# X16-ESC-Controller.net
KiCad netlist of a schematic drawn in EAGLE
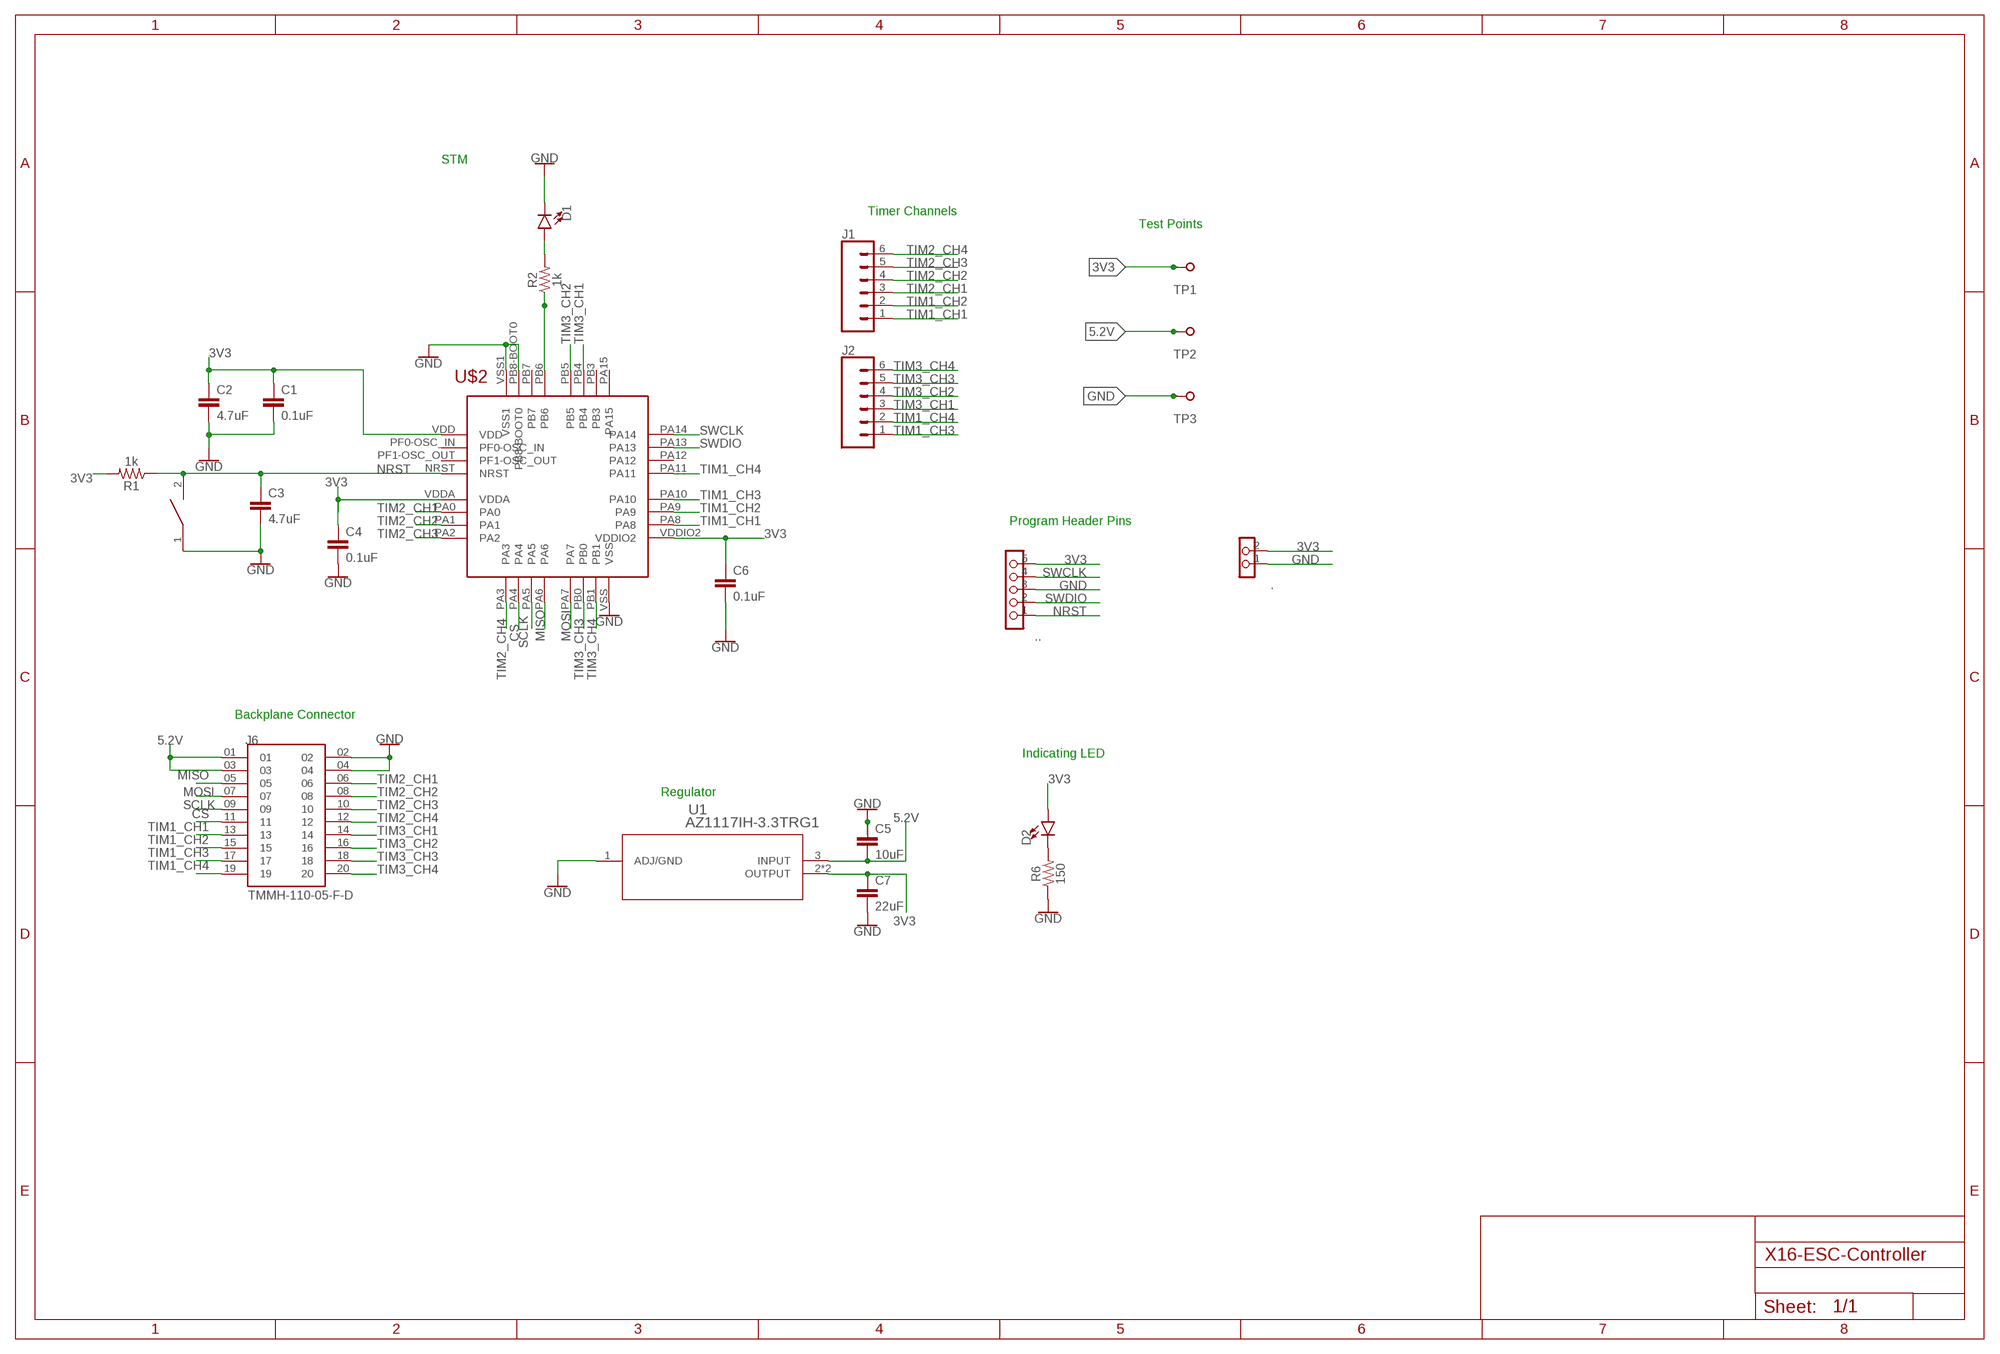
[diagram p0: schematic, sheet 1]

(export (version "E")
  (design (tool "Eeschema 10.0.6"))
  (components
    (comp (ref ".")
      (value "TEST_PIN-1X2")
      (footprint "eagle-import:1X02")
      (libsource (lib "eagle-import") (part "TEST_PIN-1X2"))
    )
    (comp (ref "..")
      (value "TEST_PIN-1X5")
      (footprint "eagle-import:1X05")
      (libsource (lib "eagle-import") (part "TEST_PIN-1X5"))
    )
    (comp (ref "C1")
      (value "0.1uF")
      (footprint "eagle-import:0603")
      (libsource (lib "eagle-import") (part "4.7PF-0603-50V-5%"))
    )
    (comp (ref "C2")
      (value "4.7uF")
      (footprint "eagle-import:0603")
      (libsource (lib "eagle-import") (part "4.7PF-0603-50V-5%"))
    )
    (comp (ref "C3")
      (value "4.7uF")
      (footprint "eagle-import:0603")
      (libsource (lib "eagle-import") (part "4.7PF-0603-50V-5%"))
    )
    (comp (ref "C4")
      (value "0.1uF")
      (footprint "eagle-import:0603")
      (libsource (lib "eagle-import") (part "4.7PF-0603-50V-5%"))
    )
    (comp (ref "C5")
      (value "10uF")
      (footprint "eagle-import:0603")
      (libsource (lib "eagle-import") (part "4.7PF-0603-50V-5%"))
    )
    (comp (ref "C6")
      (value "0.1uF")
      (footprint "eagle-import:0603")
      (libsource (lib "eagle-import") (part "4.7PF-0603-50V-5%"))
    )
    (comp (ref "C7")
      (value "22uF")
      (footprint "eagle-import:0603")
      (libsource (lib "eagle-import") (part "4.7PF-0603-50V-5%"))
    )
    (comp (ref "D1")
      (value "Green")
      (footprint "eagle-import:LED-0805")
      (libsource (lib "eagle-import") (part "LED-GREEN0805-PG"))
    )
    (comp (ref "D2")
      (value "Green")
      (footprint "eagle-import:LED-0805")
      (libsource (lib "eagle-import") (part "LED-GREEN0805-PG"))
    )
    (comp (ref "J1")
      (value "CONN_06NO_SILK_NO_POP")
      (footprint "eagle-import:1X06_NO_SILK")
      (libsource (lib "eagle-import") (part "CONN_06NO_SILK_NO_POP"))
    )
    (comp (ref "J2")
      (value "CONN_06NO_SILK_NO_POP")
      (footprint "eagle-import:1X06_NO_SILK")
      (libsource (lib "eagle-import") (part "CONN_06NO_SILK_NO_POP"))
    )
    (comp (ref "J6")
      (value "TMMH-110-05-F-D")
      (footprint "eagle-import:SAMTEC_TMMH-110-05-F-D")
      (fields (field (name "MANUFACTURER") "Samtec"))
      (libsource (lib "eagle-import") (part "TMMH-110-05-F-D"))
    )
    (comp (ref "R1")
      (value "1k")
      (footprint "eagle-import:0603")
      (libsource (lib "eagle-import") (part "2.55KOHM-0603-1/10W-1%"))
    )
    (comp (ref "R2")
      (value "1k")
      (footprint "eagle-import:0603")
      (libsource (lib "eagle-import") (part "2.55KOHM-0603-1/10W-1%"))
    )
    (comp (ref "R6")
      (value "150")
      (footprint "eagle-import:0603")
      (libsource (lib "eagle-import") (part "2.55KOHM-0603-1/10W-1%"))
    )
    (comp (ref "TP1")
      (value "TESTPOINT_5.04MM")
      (footprint "eagle-import:TESTPOINT_5.04MM")
      (libsource (lib "eagle-import") (part "TESTPOINT_5.04MM"))
    )
    (comp (ref "TP2")
      (value "TESTPOINT_5.04MM")
      (footprint "eagle-import:TESTPOINT_5.04MM")
      (libsource (lib "eagle-import") (part "TESTPOINT_5.04MM"))
    )
    (comp (ref "TP3")
      (value "TESTPOINT_5.04MM")
      (footprint "eagle-import:TESTPOINT_5.04MM")
      (libsource (lib "eagle-import") (part "TESTPOINT_5.04MM"))
    )
    (comp (ref "U$2")
      (value "IC_STM32F042K6T6")
      (footprint "eagle-import:STM32F042K6T6")
      (libsource (lib "eagle-import") (part "IC_STM32F042K6T6"))
    )
    (comp (ref "U$3")
      (value "SWITCH_DISCRETECOMPONENTS")
      (footprint "eagle-import:DISCRETECOMPONENTS_SW_2512")
      (libsource (lib "eagle-import") (part "SWITCH_DISCRETECOMPONENTS"))
    )
    (comp (ref "U1")
      (value "AZ1117IH-3.3TRG1")
      (footprint "eagle-import:SOT223_AZ1117I_6P5X3P5_DIO")
      (fields (field (name "COPYRIGHT") "Copyright (C) 2023 Ultra Librarian. All rights reserved."))
      (libsource (lib "eagle-import") (part "AZ1117IH-3.3TRG1"))
    )
  )
  (nets
    (net (code "1") (name "/CS") (class "Default")
      (node (ref "J6") (pin "11") (pinfunction "11_11") (pintype "passive"))
      (node (ref "U$2") (pin "PA4") (pinfunction "PA4_PA4") (pintype "bidirectional"))
    )
    (net (code "2") (name "/MISO") (class "Default")
      (node (ref "J6") (pin "05") (pinfunction "05_05") (pintype "passive"))
      (node (ref "U$2") (pin "PA6") (pinfunction "PA6_PA6") (pintype "bidirectional"))
    )
    (net (code "3") (name "/MOSI") (class "Default")
      (node (ref "J6") (pin "07") (pinfunction "07_07") (pintype "passive"))
      (node (ref "U$2") (pin "PA7") (pinfunction "PA7_PA7") (pintype "bidirectional"))
    )
    (net (code "4") (name "/NRST") (class "Default")
      (node (ref "..") (pin "1") (pinfunction "1_1") (pintype "passive"))
      (node (ref "C3") (pin "1") (pinfunction "1_1") (pintype "passive"))
      (node (ref "R1") (pin "1") (pinfunction "1_1") (pintype "passive"))
      (node (ref "U$2") (pin "NRST") (pinfunction "NRST_NRST") (pintype "bidirectional"))
      (node (ref "U$3") (pin "2") (pinfunction "P$2_2") (pintype "bidirectional"))
    )
    (net (code "5") (name "/SCLK") (class "Default")
      (node (ref "J6") (pin "09") (pinfunction "09_09") (pintype "passive"))
      (node (ref "U$2") (pin "PA5") (pinfunction "PA5_PA5") (pintype "bidirectional"))
    )
    (net (code "6") (name "/SWCLK") (class "Default")
      (node (ref "..") (pin "4") (pinfunction "4_4") (pintype "passive"))
      (node (ref "U$2") (pin "PA14") (pinfunction "PA14_PA14") (pintype "bidirectional"))
    )
    (net (code "7") (name "/SWDIO") (class "Default")
      (node (ref "..") (pin "2") (pinfunction "2_2") (pintype "passive"))
      (node (ref "U$2") (pin "PA13") (pinfunction "PA13_PA13") (pintype "bidirectional"))
    )
    (net (code "8") (name "/TIM1_CH1") (class "Default")
      (node (ref "J1") (pin "1") (pinfunction "1_1") (pintype "passive"))
      (node (ref "J6") (pin "13") (pinfunction "13_13") (pintype "passive"))
      (node (ref "U$2") (pin "PA8") (pinfunction "PA8_PA8") (pintype "bidirectional"))
    )
    (net (code "9") (name "/TIM1_CH2") (class "Default")
      (node (ref "J1") (pin "2") (pinfunction "2_2") (pintype "passive"))
      (node (ref "J6") (pin "15") (pinfunction "15_15") (pintype "passive"))
      (node (ref "U$2") (pin "PA9") (pinfunction "PA9_PA9") (pintype "bidirectional"))
    )
    (net (code "10") (name "/TIM1_CH3") (class "Default")
      (node (ref "J2") (pin "1") (pinfunction "1_1") (pintype "passive"))
      (node (ref "J6") (pin "17") (pinfunction "17_17") (pintype "passive"))
      (node (ref "U$2") (pin "PA10") (pinfunction "PA10_PA10") (pintype "bidirectional"))
    )
    (net (code "11") (name "/TIM1_CH4") (class "Default")
      (node (ref "J2") (pin "2") (pinfunction "2_2") (pintype "passive"))
      (node (ref "J6") (pin "19") (pinfunction "19_19") (pintype "passive"))
      (node (ref "U$2") (pin "PA11") (pinfunction "PA11_PA11") (pintype "bidirectional"))
    )
    (net (code "12") (name "/TIM2_CH1") (class "Default")
      (node (ref "J1") (pin "3") (pinfunction "3_3") (pintype "passive"))
      (node (ref "J6") (pin "06") (pinfunction "06_06") (pintype "passive"))
      (node (ref "U$2") (pin "PA0") (pinfunction "PA0_PA0") (pintype "bidirectional"))
    )
    (net (code "13") (name "/TIM2_CH2") (class "Default")
      (node (ref "J1") (pin "4") (pinfunction "4_4") (pintype "passive"))
      (node (ref "J6") (pin "08") (pinfunction "08_08") (pintype "passive"))
      (node (ref "U$2") (pin "PA1") (pinfunction "PA1_PA1") (pintype "bidirectional"))
    )
    (net (code "14") (name "/TIM2_CH3") (class "Default")
      (node (ref "J1") (pin "5") (pinfunction "5_5") (pintype "passive"))
      (node (ref "J6") (pin "10") (pinfunction "10_10") (pintype "passive"))
      (node (ref "U$2") (pin "PA2") (pinfunction "PA2_PA2") (pintype "bidirectional"))
    )
    (net (code "15") (name "/TIM2_CH4") (class "Default")
      (node (ref "J1") (pin "6") (pinfunction "6_6") (pintype "passive"))
      (node (ref "J6") (pin "12") (pinfunction "12_12") (pintype "passive"))
      (node (ref "U$2") (pin "PA3") (pinfunction "PA3_PA3") (pintype "bidirectional"))
    )
    (net (code "16") (name "/TIM3_CH1") (class "Default")
      (node (ref "J2") (pin "3") (pinfunction "3_3") (pintype "passive"))
      (node (ref "J6") (pin "14") (pinfunction "14_14") (pintype "passive"))
      (node (ref "U$2") (pin "PB4") (pinfunction "PB4_PB4") (pintype "bidirectional"))
    )
    (net (code "17") (name "/TIM3_CH2") (class "Default")
      (node (ref "J2") (pin "4") (pinfunction "4_4") (pintype "passive"))
      (node (ref "J6") (pin "16") (pinfunction "16_16") (pintype "passive"))
      (node (ref "U$2") (pin "PB5") (pinfunction "PB5_PB5") (pintype "bidirectional"))
    )
    (net (code "18") (name "/TIM3_CH3") (class "Default")
      (node (ref "J2") (pin "5") (pinfunction "5_5") (pintype "passive"))
      (node (ref "J6") (pin "18") (pinfunction "18_18") (pintype "passive"))
      (node (ref "U$2") (pin "PB0") (pinfunction "PB0_PB0") (pintype "bidirectional"))
    )
    (net (code "19") (name "/TIM3_CH4") (class "Default")
      (node (ref "J2") (pin "6") (pinfunction "6_6") (pintype "passive"))
      (node (ref "J6") (pin "20") (pinfunction "20_20") (pintype "passive"))
      (node (ref "U$2") (pin "PB1") (pinfunction "PB1_PB1") (pintype "bidirectional"))
    )
    (net (code "20") (name "3V3") (class "Default")
      (node (ref ".") (pin "2") (pinfunction "2_2") (pintype "passive"))
      (node (ref "..") (pin "5") (pinfunction "5_5") (pintype "passive"))
      (node (ref "C1") (pin "1") (pinfunction "1_1") (pintype "passive"))
      (node (ref "C2") (pin "1") (pinfunction "1_1") (pintype "passive"))
      (node (ref "C4") (pin "1") (pinfunction "1_1") (pintype "passive"))
      (node (ref "C6") (pin "1") (pinfunction "1_1") (pintype "passive"))
      (node (ref "C7") (pin "1") (pinfunction "1_1") (pintype "passive"))
      (node (ref "D2") (pin "A") (pinfunction "A_A") (pintype "passive"))
      (node (ref "R1") (pin "2") (pinfunction "2_2") (pintype "passive"))
      (node (ref "TP1") (pin "TP") (pinfunction "TP_TP") (pintype "input"))
      (node (ref "U$2") (pin "VDD") (pinfunction "VDD_VDD") (pintype "bidirectional"))
      (node (ref "U$2") (pin "VDDA") (pinfunction "VDDA_VDDA") (pintype "bidirectional"))
      (node (ref "U$2") (pin "VDDIO2") (pinfunction "VDDIO2_VDDIO2") (pintype "bidirectional"))
      (node (ref "U1") (pin "2") (pinfunction "OUTPUT_2") (pintype "output"))
      (node (ref "U1") (pin "4") (pinfunction "OUTPUT_4") (pintype "output"))
    )
    (net (code "21") (name "5.2V") (class "Default")
      (node (ref "C5") (pin "2") (pinfunction "2_2") (pintype "passive"))
      (node (ref "J6") (pin "01") (pinfunction "01_01") (pintype "passive"))
      (node (ref "J6") (pin "03") (pinfunction "03_03") (pintype "passive"))
      (node (ref "TP2") (pin "TP") (pinfunction "TP_TP") (pintype "input"))
      (node (ref "U1") (pin "3") (pinfunction "INPUT_3") (pintype "passive"))
    )
    (net (code "22") (name "GND") (class "Default")
      (node (ref ".") (pin "1") (pinfunction "1_1") (pintype "passive"))
      (node (ref "..") (pin "3") (pinfunction "3_3") (pintype "passive"))
      (node (ref "C1") (pin "2") (pinfunction "2_2") (pintype "passive"))
      (node (ref "C2") (pin "2") (pinfunction "2_2") (pintype "passive"))
      (node (ref "C3") (pin "2") (pinfunction "2_2") (pintype "passive"))
      (node (ref "C4") (pin "2") (pinfunction "2_2") (pintype "passive"))
      (node (ref "C5") (pin "1") (pinfunction "1_1") (pintype "passive"))
      (node (ref "C6") (pin "2") (pinfunction "2_2") (pintype "passive"))
      (node (ref "C7") (pin "2") (pinfunction "2_2") (pintype "passive"))
      (node (ref "D1") (pin "C") (pinfunction "C_C") (pintype "passive"))
      (node (ref "J6") (pin "02") (pinfunction "02_02") (pintype "passive"))
      (node (ref "J6") (pin "04") (pinfunction "04_04") (pintype "passive"))
      (node (ref "R6") (pin "1") (pinfunction "1_1") (pintype "passive"))
      (node (ref "TP3") (pin "TP") (pinfunction "TP_TP") (pintype "input"))
      (node (ref "U$2") (pin "PB8-BOOT0") (pinfunction "PB8-BOOT0_PB8-BOOT0") (pintype "bidirectional"))
      (node (ref "U$2") (pin "VSS") (pinfunction "VSS_VSS") (pintype "bidirectional"))
      (node (ref "U$2") (pin "VSS1") (pinfunction "VSS1_VSS1") (pintype "bidirectional"))
      (node (ref "U$3") (pin "1") (pinfunction "P$1_1") (pintype "bidirectional"))
      (node (ref "U1") (pin "1") (pinfunction "ADJ/GND_1") (pintype "passive"))
    )
    (net (code "23") (name "Net-(D1-PadA)") (class "Default")
      (node (ref "D1") (pin "A") (pinfunction "A_A") (pintype "passive"))
      (node (ref "R2") (pin "2") (pinfunction "2_2") (pintype "passive"))
    )
    (net (code "24") (name "Net-(D2-PadC)") (class "Default")
      (node (ref "D2") (pin "C") (pinfunction "C_C") (pintype "passive"))
      (node (ref "R6") (pin "2") (pinfunction "2_2") (pintype "passive"))
    )
    (net (code "25") (name "Net-(R2-Pad1)") (class "Default")
      (node (ref "R2") (pin "1") (pinfunction "1_1") (pintype "passive"))
      (node (ref "U$2") (pin "PB6") (pinfunction "PB6_PB6") (pintype "bidirectional"))
    )
    (net (code "26") (name "unconnected-(U$2-PadPA12)") (class "Default")
      (node (ref "U$2") (pin "PA12") (pinfunction "PA12_PA12") (pintype "bidirectional"))
    )
    (net (code "27") (name "unconnected-(U$2-PadPA15)") (class "Default")
      (node (ref "U$2") (pin "PA15") (pinfunction "PA15_PA15") (pintype "bidirectional"))
    )
    (net (code "28") (name "unconnected-(U$2-PadPB3)") (class "Default")
      (node (ref "U$2") (pin "PB3") (pinfunction "PB3_PB3") (pintype "bidirectional"))
    )
    (net (code "29") (name "unconnected-(U$2-PadPB7)") (class "Default")
      (node (ref "U$2") (pin "PB7") (pinfunction "PB7_PB7") (pintype "bidirectional"))
    )
    (net (code "30") (name "unconnected-(U$2-PadPF0-OSC_IN)") (class "Default")
      (node (ref "U$2") (pin "PF0-OSC_IN") (pinfunction "PF0-OSC_IN_PF0-OSC_IN") (pintype "bidirectional"))
    )
    (net (code "31") (name "unconnected-(U$2-PadPF1-OSC_OUT)") (class "Default")
      (node (ref "U$2") (pin "PF1-OSC_OUT") (pinfunction "PF1-OSC_OUT_PF1-OSC_OUT") (pintype "bidirectional"))
    )
  )
)
